# 1-Schematic_Automatic_watering_Pump_shie.net
KiCad netlist of a schematic drawn in EasyEDA
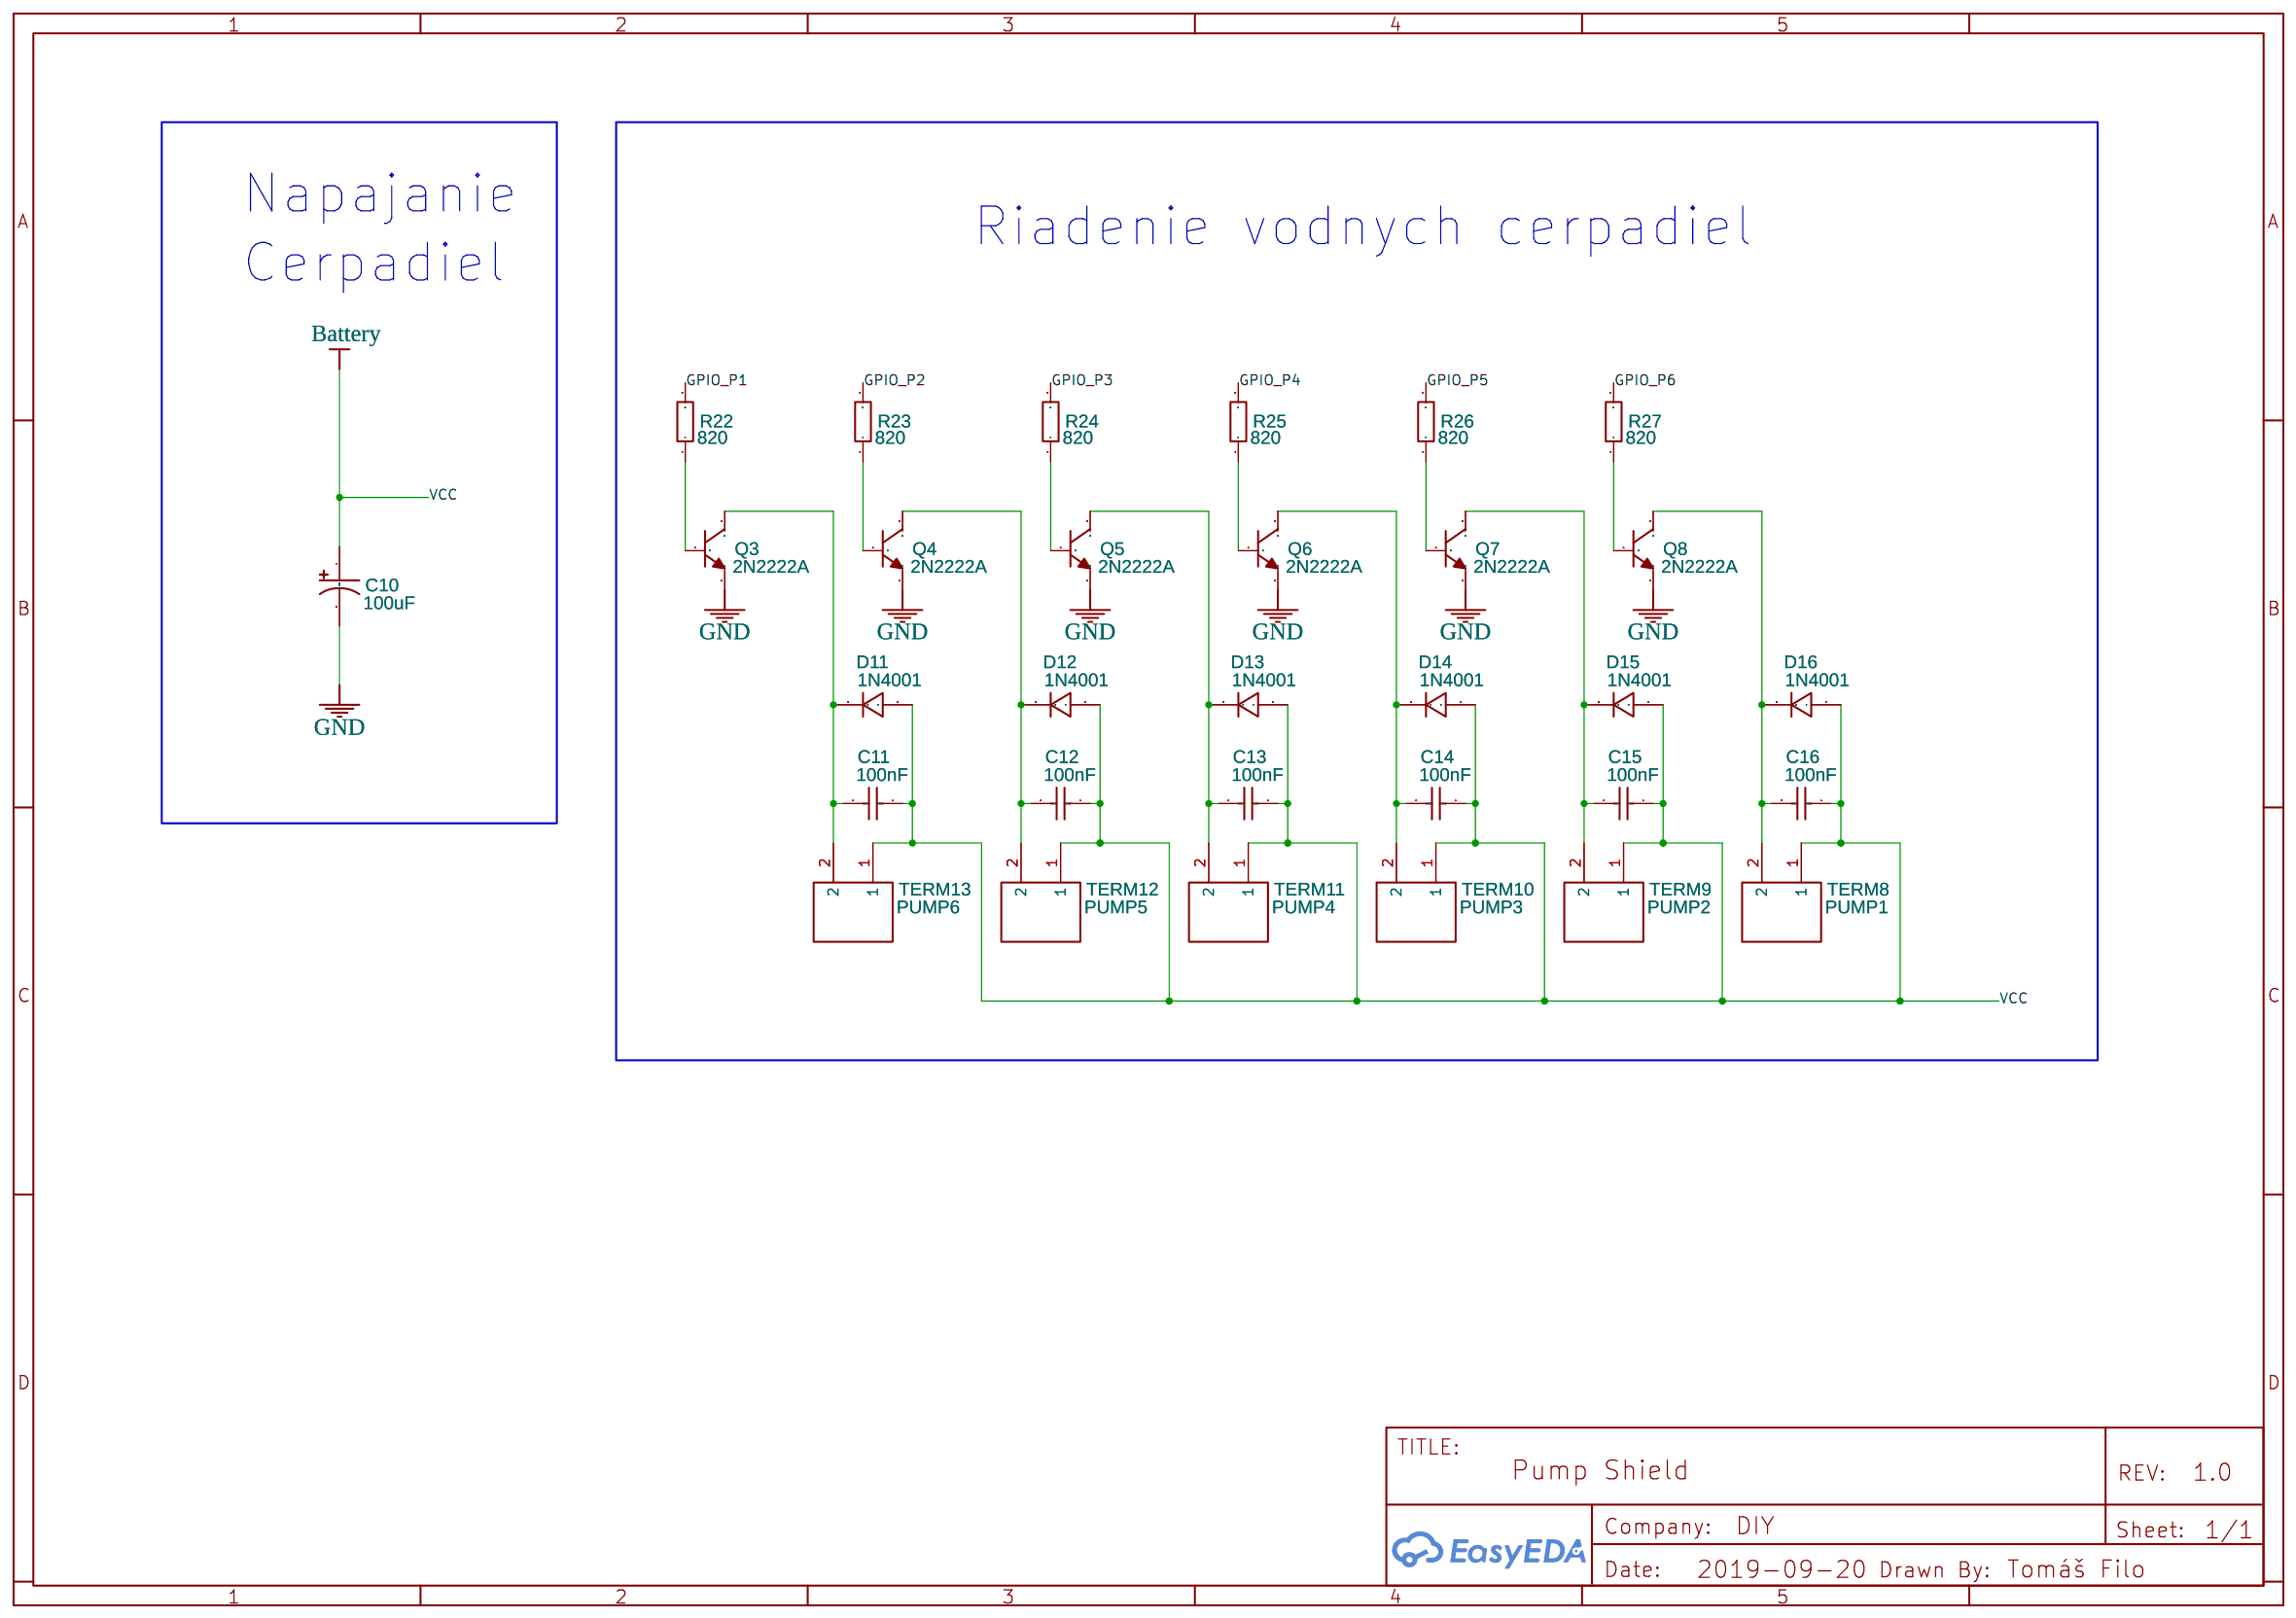
[diagram p0: schematic sheet]

(export (version "E")
  (design (tool "Eeschema 10.0.6"))
  (components
    (comp (ref "C10")
      (value "100uF")
      (fields
        (field (name "BOM_Manufacturer Part") "SMS25VB47M5*11_5.0TP")
        (field (name "BOM_Supplier Part") "C371229")
      )
      (libsource (lib "") (part "SMS25VB47M5*11_5.0TP"))
    )
    (comp (ref "C11")
      (value "100nF")
      (fields
        (field (name "BOM_Manufacturer Part") "CD1H224KC9BER1E000")
        (field (name "BOM_Supplier Part") "C263191")
      )
      (libsource (lib "") (part "CD1H224KC9BER1E000"))
    )
    (comp (ref "C12")
      (value "100nF")
      (fields
        (field (name "BOM_Manufacturer Part") "CD1H224KC9BER1E000")
        (field (name "BOM_Supplier Part") "C263191")
      )
      (libsource (lib "") (part "CD1H224KC9BER1E000"))
    )
    (comp (ref "C13")
      (value "100nF")
      (fields
        (field (name "BOM_Manufacturer Part") "CD1H224KC9BER1E000")
        (field (name "BOM_Supplier Part") "C263191")
      )
      (libsource (lib "") (part "CD1H224KC9BER1E000"))
    )
    (comp (ref "C14")
      (value "100nF")
      (fields
        (field (name "BOM_Manufacturer Part") "CD1H224KC9BER1E000")
        (field (name "BOM_Supplier Part") "C263191")
      )
      (libsource (lib "") (part "CD1H224KC9BER1E000"))
    )
    (comp (ref "C15")
      (value "100nF")
      (fields
        (field (name "BOM_Manufacturer Part") "CD1H224KC9BER1E000")
        (field (name "BOM_Supplier Part") "C263191")
      )
      (libsource (lib "") (part "CD1H224KC9BER1E000"))
    )
    (comp (ref "C16")
      (value "100nF")
      (fields
        (field (name "BOM_Manufacturer Part") "CD1H224KC9BER1E000")
        (field (name "BOM_Supplier Part") "C263191")
      )
      (libsource (lib "") (part "CD1H224KC9BER1E000"))
    )
    (comp (ref "D11")
      (value "1N4001")
      (fields (field (name "BOM_Supplier Part") "C169150"))
      (libsource (lib "") (part "Unknown_435_350"))
    )
    (comp (ref "D12")
      (value "1N4001")
      (fields (field (name "BOM_Supplier Part") "C169150"))
      (libsource (lib "") (part "Unknown_530_350"))
    )
    (comp (ref "D13")
      (value "1N4001")
      (fields (field (name "BOM_Supplier Part") "C169150"))
      (libsource (lib "") (part "Unknown_625_350"))
    )
    (comp (ref "D14")
      (value "1N4001")
      (fields (field (name "BOM_Supplier Part") "C169150"))
      (libsource (lib "") (part "Unknown_720_350"))
    )
    (comp (ref "D15")
      (value "1N4001")
      (fields (field (name "BOM_Supplier Part") "C169150"))
      (libsource (lib "") (part "Unknown_815_350"))
    )
    (comp (ref "D16")
      (value "1N4001")
      (fields (field (name "BOM_Supplier Part") "C169150"))
      (libsource (lib "") (part "Unknown_905_350"))
    )
    (comp (ref "Q3")
      (value "2N2222A")
      (fields (field (name "BOM_Supplier Part") "C358533"))
      (libsource (lib "") (part "Unknown_350_272"))
    )
    (comp (ref "Q4")
      (value "2N2222A")
      (fields (field (name "BOM_Supplier Part") "C358533"))
      (libsource (lib "") (part "Unknown_440_272"))
    )
    (comp (ref "Q5")
      (value "2N2222A")
      (fields (field (name "BOM_Supplier Part") "C358533"))
      (libsource (lib "") (part "Unknown_535_272"))
    )
    (comp (ref "Q6")
      (value "2N2222A")
      (fields (field (name "BOM_Supplier Part") "C358533"))
      (libsource (lib "") (part "Unknown_630_272"))
    )
    (comp (ref "Q7")
      (value "2N2222A")
      (fields (field (name "BOM_Supplier Part") "C358533"))
      (libsource (lib "") (part "Unknown_725_272"))
    )
    (comp (ref "Q8")
      (value "2N2222A")
      (fields (field (name "BOM_Supplier Part") "C358533"))
      (libsource (lib "") (part "Unknown_820_272"))
    )
    (comp (ref "R22")
      (value "820")
      (fields (field (name "BOM_Supplier Part") "C119313"))
      (libsource (lib "") (part "MF1/4W-330Ω±1% T52"))
    )
    (comp (ref "R23")
      (value "820")
      (fields (field (name "BOM_Supplier Part") "C119313"))
      (libsource (lib "") (part "MF1/4W-330Ω±1% T52"))
    )
    (comp (ref "R24")
      (value "820")
      (fields (field (name "BOM_Supplier Part") "C119313"))
      (libsource (lib "") (part "MF1/4W-330Ω±1% T52"))
    )
    (comp (ref "R25")
      (value "820")
      (fields (field (name "BOM_Supplier Part") "C119313"))
      (libsource (lib "") (part "MF1/4W-330Ω±1% T52"))
    )
    (comp (ref "R26")
      (value "820")
      (fields (field (name "BOM_Supplier Part") "C119313"))
      (libsource (lib "") (part "MF1/4W-330Ω±1% T52"))
    )
    (comp (ref "R27")
      (value "820")
      (fields (field (name "BOM_Supplier Part") "C119313"))
      (libsource (lib "") (part "MF1/4W-330Ω±1% T52"))
    )
    (comp (ref "TERM8")
      (value "PUMP1")
      (fields
        (field (name "BOM_Manufacturer Part") "MKDSN1.5/2-5.08")
        (field (name "BOM_Supplier Part") "C91153")
      )
      (libsource (lib "") (part "Unknown_895_445"))
    )
    (comp (ref "TERM9")
      (value "PUMP2")
      (fields
        (field (name "BOM_Manufacturer Part") "MKDSN1.5/2-5.08")
        (field (name "BOM_Supplier Part") "C91153")
      )
      (libsource (lib "") (part "Unknown_805_445"))
    )
    (comp (ref "TERM10")
      (value "PUMP3")
      (fields
        (field (name "BOM_Manufacturer Part") "MKDSN1.5/2-5.08")
        (field (name "BOM_Supplier Part") "C91153")
      )
      (libsource (lib "") (part "Unknown_710_445"))
    )
    (comp (ref "TERM11")
      (value "PUMP4")
      (fields
        (field (name "BOM_Manufacturer Part") "MKDSN1.5/2-5.08")
        (field (name "BOM_Supplier Part") "C91153")
      )
      (libsource (lib "") (part "Unknown_615_445"))
    )
    (comp (ref "TERM12")
      (value "PUMP5")
      (fields
        (field (name "BOM_Manufacturer Part") "MKDSN1.5/2-5.08")
        (field (name "BOM_Supplier Part") "C91153")
      )
      (libsource (lib "") (part "Unknown_520_445"))
    )
    (comp (ref "TERM13")
      (value "PUMP6")
      (fields
        (field (name "BOM_Manufacturer Part") "MKDSN1.5/2-5.08")
        (field (name "BOM_Supplier Part") "C91153")
      )
      (libsource (lib "") (part "Unknown_425_445"))
    )
  )
  (nets
    (net (code "1") (name "/GPIO_P1") (class "Default")
      (node (ref "R22") (pin "2") (pinfunction "2_2") (pintype "unspecified"))
    )
    (net (code "2") (name "/GPIO_P2") (class "Default")
      (node (ref "R23") (pin "2") (pinfunction "2_2") (pintype "unspecified"))
    )
    (net (code "3") (name "/GPIO_P3") (class "Default")
      (node (ref "R24") (pin "2") (pinfunction "2_2") (pintype "unspecified"))
    )
    (net (code "4") (name "/GPIO_P4") (class "Default")
      (node (ref "R25") (pin "2") (pinfunction "2_2") (pintype "unspecified"))
    )
    (net (code "5") (name "/GPIO_P5") (class "Default")
      (node (ref "R26") (pin "2") (pinfunction "2_2") (pintype "unspecified"))
    )
    (net (code "6") (name "/GPIO_P6") (class "Default")
      (node (ref "R27") (pin "2") (pinfunction "2_2") (pintype "unspecified"))
    )
    (net (code "7") (name "Battery") (class "Default")
      (node (ref "C10") (pin "1") (pinfunction "1_1") (pintype "unspecified"))
      (node (ref "C11") (pin "1") (pinfunction "1_1") (pintype "input"))
      (node (ref "C12") (pin "1") (pinfunction "1_1") (pintype "input"))
      (node (ref "C13") (pin "1") (pinfunction "1_1") (pintype "input"))
      (node (ref "C14") (pin "1") (pinfunction "1_1") (pintype "input"))
      (node (ref "C15") (pin "1") (pinfunction "1_1") (pintype "input"))
      (node (ref "C16") (pin "1") (pinfunction "1_1") (pintype "input"))
      (node (ref "D11") (pin "1") (pinfunction "1_1") (pintype "unspecified"))
      (node (ref "D12") (pin "1") (pinfunction "1_1") (pintype "unspecified"))
      (node (ref "D13") (pin "1") (pinfunction "1_1") (pintype "unspecified"))
      (node (ref "D14") (pin "1") (pinfunction "1_1") (pintype "unspecified"))
      (node (ref "D15") (pin "1") (pinfunction "1_1") (pintype "unspecified"))
      (node (ref "D16") (pin "1") (pinfunction "1_1") (pintype "unspecified"))
      (node (ref "TERM10") (pin "1") (pinfunction "1_1") (pintype "unspecified"))
      (node (ref "TERM11") (pin "1") (pinfunction "1_1") (pintype "unspecified"))
      (node (ref "TERM12") (pin "1") (pinfunction "1_1") (pintype "unspecified"))
      (node (ref "TERM13") (pin "1") (pinfunction "1_1") (pintype "unspecified"))
      (node (ref "TERM8") (pin "1") (pinfunction "1_1") (pintype "unspecified"))
      (node (ref "TERM9") (pin "1") (pinfunction "1_1") (pintype "unspecified"))
    )
    (net (code "8") (name "GND") (class "Default")
      (node (ref "C10") (pin "2") (pinfunction "2_2") (pintype "unspecified"))
      (node (ref "Q3") (pin "3") (pinfunction "E_3") (pintype "unspecified"))
      (node (ref "Q4") (pin "3") (pinfunction "E_3") (pintype "unspecified"))
      (node (ref "Q5") (pin "3") (pinfunction "E_3") (pintype "unspecified"))
      (node (ref "Q6") (pin "3") (pinfunction "E_3") (pintype "unspecified"))
      (node (ref "Q7") (pin "3") (pinfunction "E_3") (pintype "unspecified"))
      (node (ref "Q8") (pin "3") (pinfunction "E_3") (pintype "unspecified"))
    )
    (net (code "9") (name "Net-(Q3-B)") (class "Default")
      (node (ref "Q3") (pin "2") (pinfunction "B_2") (pintype "unspecified"))
      (node (ref "R22") (pin "1") (pinfunction "1_1") (pintype "unspecified"))
    )
    (net (code "10") (name "Net-(Q3-C)") (class "Default")
      (node (ref "C11") (pin "2") (pinfunction "2_2") (pintype "input"))
      (node (ref "D11") (pin "2") (pinfunction "2_2") (pintype "unspecified"))
      (node (ref "Q3") (pin "1") (pinfunction "C_1") (pintype "unspecified"))
      (node (ref "TERM13") (pin "2") (pinfunction "2_2") (pintype "unspecified"))
    )
    (net (code "11") (name "Net-(Q4-B)") (class "Default")
      (node (ref "Q4") (pin "2") (pinfunction "B_2") (pintype "unspecified"))
      (node (ref "R23") (pin "1") (pinfunction "1_1") (pintype "unspecified"))
    )
    (net (code "12") (name "Net-(Q4-C)") (class "Default")
      (node (ref "C12") (pin "2") (pinfunction "2_2") (pintype "input"))
      (node (ref "D12") (pin "2") (pinfunction "2_2") (pintype "unspecified"))
      (node (ref "Q4") (pin "1") (pinfunction "C_1") (pintype "unspecified"))
      (node (ref "TERM12") (pin "2") (pinfunction "2_2") (pintype "unspecified"))
    )
    (net (code "13") (name "Net-(Q5-B)") (class "Default")
      (node (ref "Q5") (pin "2") (pinfunction "B_2") (pintype "unspecified"))
      (node (ref "R24") (pin "1") (pinfunction "1_1") (pintype "unspecified"))
    )
    (net (code "14") (name "Net-(Q5-C)") (class "Default")
      (node (ref "C13") (pin "2") (pinfunction "2_2") (pintype "input"))
      (node (ref "D13") (pin "2") (pinfunction "2_2") (pintype "unspecified"))
      (node (ref "Q5") (pin "1") (pinfunction "C_1") (pintype "unspecified"))
      (node (ref "TERM11") (pin "2") (pinfunction "2_2") (pintype "unspecified"))
    )
    (net (code "15") (name "Net-(Q6-B)") (class "Default")
      (node (ref "Q6") (pin "2") (pinfunction "B_2") (pintype "unspecified"))
      (node (ref "R25") (pin "1") (pinfunction "1_1") (pintype "unspecified"))
    )
    (net (code "16") (name "Net-(Q6-C)") (class "Default")
      (node (ref "C14") (pin "2") (pinfunction "2_2") (pintype "input"))
      (node (ref "D14") (pin "2") (pinfunction "2_2") (pintype "unspecified"))
      (node (ref "Q6") (pin "1") (pinfunction "C_1") (pintype "unspecified"))
      (node (ref "TERM10") (pin "2") (pinfunction "2_2") (pintype "unspecified"))
    )
    (net (code "17") (name "Net-(Q7-B)") (class "Default")
      (node (ref "Q7") (pin "2") (pinfunction "B_2") (pintype "unspecified"))
      (node (ref "R26") (pin "1") (pinfunction "1_1") (pintype "unspecified"))
    )
    (net (code "18") (name "Net-(Q7-C)") (class "Default")
      (node (ref "C15") (pin "2") (pinfunction "2_2") (pintype "input"))
      (node (ref "D15") (pin "2") (pinfunction "2_2") (pintype "unspecified"))
      (node (ref "Q7") (pin "1") (pinfunction "C_1") (pintype "unspecified"))
      (node (ref "TERM9") (pin "2") (pinfunction "2_2") (pintype "unspecified"))
    )
    (net (code "19") (name "Net-(Q8-B)") (class "Default")
      (node (ref "Q8") (pin "2") (pinfunction "B_2") (pintype "unspecified"))
      (node (ref "R27") (pin "1") (pinfunction "1_1") (pintype "unspecified"))
    )
    (net (code "20") (name "Net-(Q8-C)") (class "Default")
      (node (ref "C16") (pin "2") (pinfunction "2_2") (pintype "input"))
      (node (ref "D16") (pin "2") (pinfunction "2_2") (pintype "unspecified"))
      (node (ref "Q8") (pin "1") (pinfunction "C_1") (pintype "unspecified"))
      (node (ref "TERM8") (pin "2") (pinfunction "2_2") (pintype "unspecified"))
    )
  )
)
